# FPGA_Bank2-3.net
KiCad netlist of a schematic drawn in Altium Designer
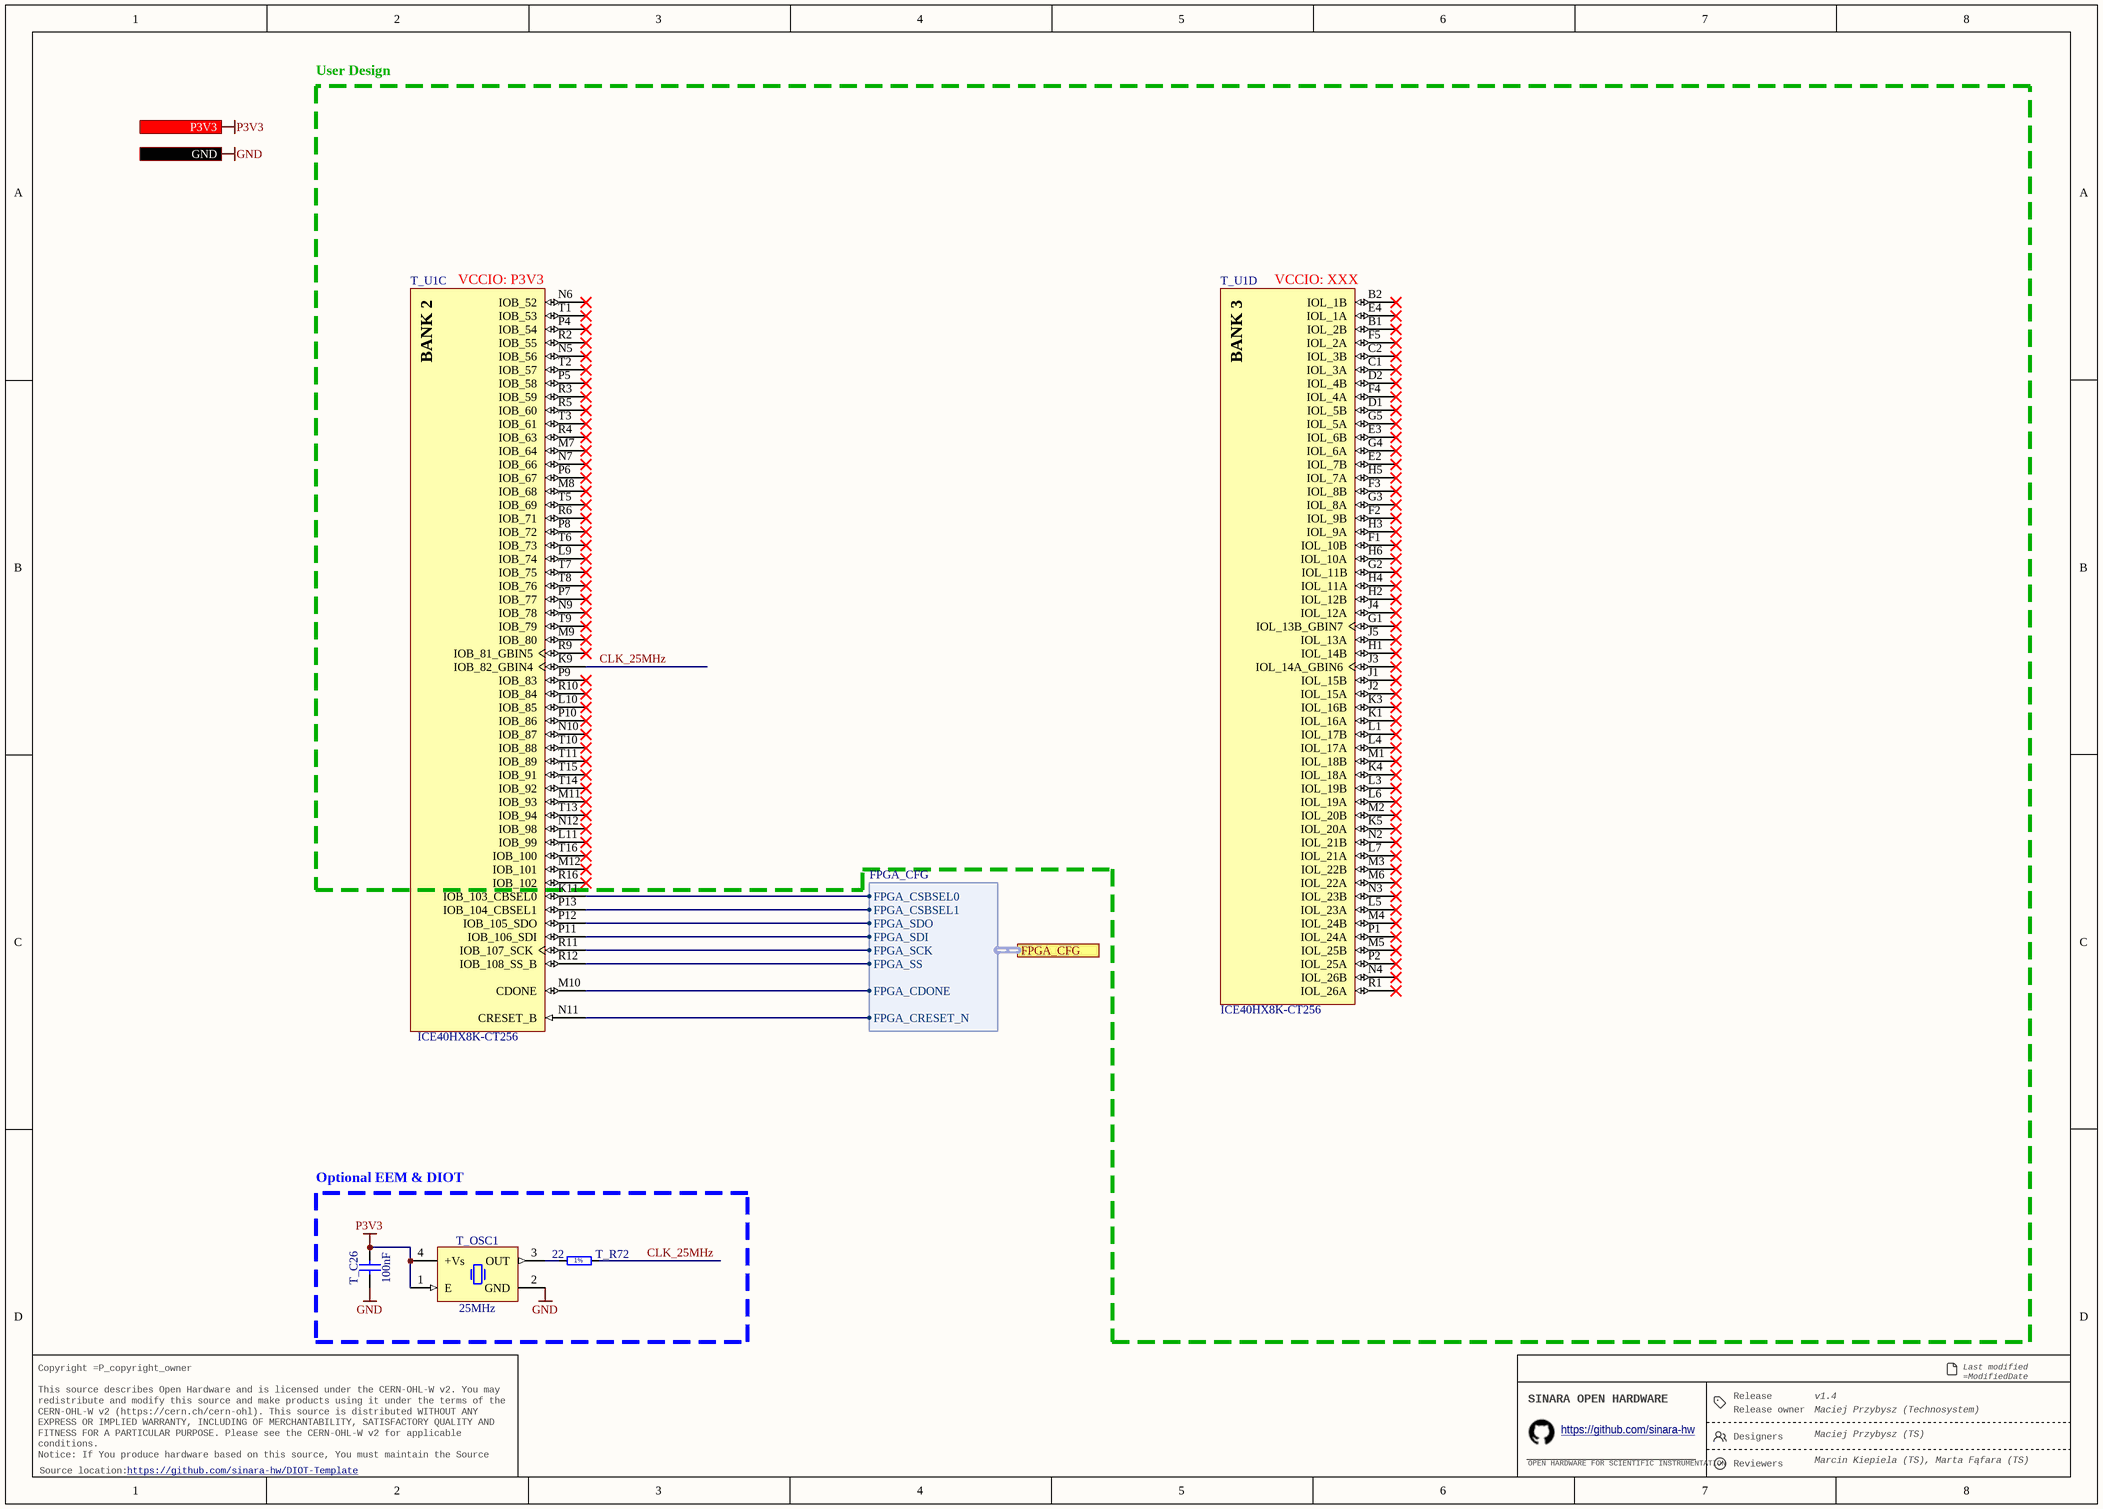
[diagram p0: FPGA_Bank2-3.SchDoc]

(export (version "E")
  (design (tool "Eeschema 10.0.6"))
  (components
    (comp (ref "T_C26")
      (value "100nF")
      (footprint "CAPC1005X55N")
      (description "Non-polarised capacitor")
      (fields
        (field (name "PART NUMBER") "CC0402_100NF_50V_10%_X7R")
        (field (name "VOLTAGE") "50V")
        (field (name "AUTHOR") "CERN DEM MR")
      )
      (libsource (lib "Capacitors") (part "Capacitor - non polarized"))
    )
    (comp (ref "T_OSC1")
      (value "25MHz")
      (footprint "OSC_IQD_CFPS-39")
      (description "Oscillator 4 pins 1=E 2=GND 3=OUT 4=+Vs")
      (fields
        (field (name "PART NUMBER") "OSC_25MHZ_IQD_LFSPXO025165")
        (field (name "MANUFACTURER") "IQD FREQUENCY PRODUCTS")
        (field (name "AUTHOR") "CERN DEM JLC")
      )
      (libsource (lib "ICs And Semiconductors") (part "Oscillator 1E 2GND 3OUT 4Vs"))
    )
    (comp (ref "T_R72")
      (value "22")
      (footprint "RESC1005X40N")
      (description "Resistor - 1%")
      (fields
        (field (name "PART NUMBER") "R0402_22R_1%_0.0625W_100PPM")
        (field (name "POWER") "0.0625W")
        (field (name "AUTHOR") "CERN DEM JLC")
      )
      (libsource (lib "Resistors") (part "Resistor - 1%"))
    )
    (comp (ref "T_U1")
      (value "ICE40HX8K-CT256")
      (footprint "LATC-caBGA-256")
      (fields (field (name "MANUFACTURER") "Lattice Semiconductor"))
      (libsource (lib "Altium Content Vault") (part "LATC-HX8K-caBGA-256"))
    )
  )
  (nets
    (net (code "2") (name "/CLK_25MHz") (class "Default")
      (node (ref "T_R72") (pin "2") (pinfunction "2_2") (pintype "passive"))
      (node (ref "T_U1") (pin "K9") (pinfunction "IOB_82_GBIN4_K9") (pintype "bidirectional"))
    )
    (net (code "3") (name "/FPGA_CDONE") (class "Default")
      (node (ref "T_U1") (pin "M10") (pinfunction "CDONE_M10") (pintype "bidirectional"))
    )
    (net (code "4") (name "/FPGA_CRESET_N") (class "Default")
      (node (ref "T_U1") (pin "N11") (pinfunction "CRESET_B_N11") (pintype "input"))
    )
    (net (code "5") (name "/FPGA_CSBSEL0") (class "Default")
      (node (ref "T_U1") (pin "K11") (pinfunction "IOB_103_CBSEL0_K11") (pintype "bidirectional"))
    )
    (net (code "6") (name "/FPGA_CSBSEL1") (class "Default")
      (node (ref "T_U1") (pin "P13") (pinfunction "IOB_104_CBSEL1_P13") (pintype "bidirectional"))
    )
    (net (code "7") (name "/FPGA_SCK") (class "Default")
      (node (ref "T_U1") (pin "R11") (pinfunction "IOB_107_SCK_R11") (pintype "bidirectional"))
    )
    (net (code "8") (name "/FPGA_SDI") (class "Default")
      (node (ref "T_U1") (pin "P11") (pinfunction "IOB_106_SDI_P11") (pintype "bidirectional"))
    )
    (net (code "9") (name "/FPGA_SDO") (class "Default")
      (node (ref "T_U1") (pin "P12") (pinfunction "IOB_105_SDO_P12") (pintype "bidirectional"))
    )
    (net (code "10") (name "/FPGA_SS") (class "Default")
      (node (ref "T_U1") (pin "R12") (pinfunction "IOB_108_SS_B_R12") (pintype "bidirectional"))
    )
    (net (code "12") (name "GND") (class "Default")
      (node (ref "T_C26") (pin "1") (pinfunction "1_1") (pintype "passive"))
      (node (ref "T_OSC1") (pin "2") (pinfunction "GND_2") (pintype "power_in"))
    )
    (net (code "13") (name "Net-(T_OSC1-OUT)") (class "Default")
      (node (ref "T_OSC1") (pin "3") (pinfunction "OUT_3") (pintype "output"))
      (node (ref "T_R72") (pin "1") (pinfunction "1_1") (pintype "passive"))
    )
    (net (code "14") (name "P3V3") (class "Default")
      (node (ref "T_C26") (pin "2") (pinfunction "2_2") (pintype "passive"))
      (node (ref "T_OSC1") (pin "1") (pinfunction "E_1") (pintype "input"))
      (node (ref "T_OSC1") (pin "4") (pinfunction "+Vs_4") (pintype "power_in"))
    )
    (net (code "15") (name "unconnected-(T_U1C-IOB_52-PadN6)") (class "Default")
      (node (ref "T_U1") (pin "N6") (pinfunction "IOB_52_N6") (pintype "bidirectional+no_connect"))
    )
    (net (code "16") (name "unconnected-(T_U1C-IOB_53-PadT1)") (class "Default")
      (node (ref "T_U1") (pin "T1") (pinfunction "IOB_53_T1") (pintype "bidirectional+no_connect"))
    )
    (net (code "17") (name "unconnected-(T_U1C-IOB_54-PadP4)") (class "Default")
      (node (ref "T_U1") (pin "P4") (pinfunction "IOB_54_P4") (pintype "bidirectional+no_connect"))
    )
    (net (code "18") (name "unconnected-(T_U1C-IOB_55-PadR2)") (class "Default")
      (node (ref "T_U1") (pin "R2") (pinfunction "IOB_55_R2") (pintype "bidirectional+no_connect"))
    )
    (net (code "19") (name "unconnected-(T_U1C-IOB_56-PadN5)") (class "Default")
      (node (ref "T_U1") (pin "N5") (pinfunction "IOB_56_N5") (pintype "bidirectional+no_connect"))
    )
    (net (code "20") (name "unconnected-(T_U1C-IOB_57-PadT2)") (class "Default")
      (node (ref "T_U1") (pin "T2") (pinfunction "IOB_57_T2") (pintype "bidirectional+no_connect"))
    )
    (net (code "21") (name "unconnected-(T_U1C-IOB_58-PadP5)") (class "Default")
      (node (ref "T_U1") (pin "P5") (pinfunction "IOB_58_P5") (pintype "bidirectional+no_connect"))
    )
    (net (code "22") (name "unconnected-(T_U1C-IOB_59-PadR3)") (class "Default")
      (node (ref "T_U1") (pin "R3") (pinfunction "IOB_59_R3") (pintype "bidirectional+no_connect"))
    )
    (net (code "23") (name "unconnected-(T_U1C-IOB_60-PadR5)") (class "Default")
      (node (ref "T_U1") (pin "R5") (pinfunction "IOB_60_R5") (pintype "bidirectional+no_connect"))
    )
    (net (code "24") (name "unconnected-(T_U1C-IOB_61-PadT3)") (class "Default")
      (node (ref "T_U1") (pin "T3") (pinfunction "IOB_61_T3") (pintype "bidirectional+no_connect"))
    )
    (net (code "25") (name "unconnected-(T_U1C-IOB_63-PadR4)") (class "Default")
      (node (ref "T_U1") (pin "R4") (pinfunction "IOB_63_R4") (pintype "bidirectional+no_connect"))
    )
    (net (code "26") (name "unconnected-(T_U1C-IOB_64-PadM7)") (class "Default")
      (node (ref "T_U1") (pin "M7") (pinfunction "IOB_64_M7") (pintype "bidirectional+no_connect"))
    )
    (net (code "27") (name "unconnected-(T_U1C-IOB_66-PadN7)") (class "Default")
      (node (ref "T_U1") (pin "N7") (pinfunction "IOB_66_N7") (pintype "bidirectional+no_connect"))
    )
    (net (code "28") (name "unconnected-(T_U1C-IOB_67-PadP6)") (class "Default")
      (node (ref "T_U1") (pin "P6") (pinfunction "IOB_67_P6") (pintype "bidirectional+no_connect"))
    )
    (net (code "29") (name "unconnected-(T_U1C-IOB_68-PadM8)") (class "Default")
      (node (ref "T_U1") (pin "M8") (pinfunction "IOB_68_M8") (pintype "bidirectional+no_connect"))
    )
    (net (code "30") (name "unconnected-(T_U1C-IOB_69-PadT5)") (class "Default")
      (node (ref "T_U1") (pin "T5") (pinfunction "IOB_69_T5") (pintype "bidirectional+no_connect"))
    )
    (net (code "31") (name "unconnected-(T_U1C-IOB_71-PadR6)") (class "Default")
      (node (ref "T_U1") (pin "R6") (pinfunction "IOB_71_R6") (pintype "bidirectional+no_connect"))
    )
    (net (code "32") (name "unconnected-(T_U1C-IOB_72-PadP8)") (class "Default")
      (node (ref "T_U1") (pin "P8") (pinfunction "IOB_72_P8") (pintype "bidirectional+no_connect"))
    )
    (net (code "33") (name "unconnected-(T_U1C-IOB_73-PadT6)") (class "Default")
      (node (ref "T_U1") (pin "T6") (pinfunction "IOB_73_T6") (pintype "bidirectional+no_connect"))
    )
    (net (code "34") (name "unconnected-(T_U1C-IOB_74-PadL9)") (class "Default")
      (node (ref "T_U1") (pin "L9") (pinfunction "IOB_74_L9") (pintype "bidirectional+no_connect"))
    )
    (net (code "35") (name "unconnected-(T_U1C-IOB_75-PadT7)") (class "Default")
      (node (ref "T_U1") (pin "T7") (pinfunction "IOB_75_T7") (pintype "bidirectional+no_connect"))
    )
    (net (code "36") (name "unconnected-(T_U1C-IOB_76-PadT8)") (class "Default")
      (node (ref "T_U1") (pin "T8") (pinfunction "IOB_76_T8") (pintype "bidirectional+no_connect"))
    )
    (net (code "37") (name "unconnected-(T_U1C-IOB_77-PadP7)") (class "Default")
      (node (ref "T_U1") (pin "P7") (pinfunction "IOB_77_P7") (pintype "bidirectional+no_connect"))
    )
    (net (code "38") (name "unconnected-(T_U1C-IOB_78-PadN9)") (class "Default")
      (node (ref "T_U1") (pin "N9") (pinfunction "IOB_78_N9") (pintype "bidirectional+no_connect"))
    )
    (net (code "39") (name "unconnected-(T_U1C-IOB_79-PadT9)") (class "Default")
      (node (ref "T_U1") (pin "T9") (pinfunction "IOB_79_T9") (pintype "bidirectional+no_connect"))
    )
    (net (code "40") (name "unconnected-(T_U1C-IOB_80-PadM9)") (class "Default")
      (node (ref "T_U1") (pin "M9") (pinfunction "IOB_80_M9") (pintype "bidirectional+no_connect"))
    )
    (net (code "41") (name "unconnected-(T_U1C-IOB_81_GBIN5-PadR9)") (class "Default")
      (node (ref "T_U1") (pin "R9") (pinfunction "IOB_81_GBIN5_R9") (pintype "bidirectional+no_connect"))
    )
    (net (code "42") (name "unconnected-(T_U1C-IOB_83-PadP9)") (class "Default")
      (node (ref "T_U1") (pin "P9") (pinfunction "IOB_83_P9") (pintype "bidirectional+no_connect"))
    )
    (net (code "43") (name "unconnected-(T_U1C-IOB_84-PadR10)") (class "Default")
      (node (ref "T_U1") (pin "R10") (pinfunction "IOB_84_R10") (pintype "bidirectional+no_connect"))
    )
    (net (code "44") (name "unconnected-(T_U1C-IOB_85-PadL10)") (class "Default")
      (node (ref "T_U1") (pin "L10") (pinfunction "IOB_85_L10") (pintype "bidirectional+no_connect"))
    )
    (net (code "45") (name "unconnected-(T_U1C-IOB_86-PadP10)") (class "Default")
      (node (ref "T_U1") (pin "P10") (pinfunction "IOB_86_P10") (pintype "bidirectional+no_connect"))
    )
    (net (code "46") (name "unconnected-(T_U1C-IOB_87-PadN10)") (class "Default")
      (node (ref "T_U1") (pin "N10") (pinfunction "IOB_87_N10") (pintype "bidirectional+no_connect"))
    )
    (net (code "47") (name "unconnected-(T_U1C-IOB_88-PadT10)") (class "Default")
      (node (ref "T_U1") (pin "T10") (pinfunction "IOB_88_T10") (pintype "bidirectional+no_connect"))
    )
    (net (code "48") (name "unconnected-(T_U1C-IOB_89-PadT11)") (class "Default")
      (node (ref "T_U1") (pin "T11") (pinfunction "IOB_89_T11") (pintype "bidirectional+no_connect"))
    )
    (net (code "49") (name "unconnected-(T_U1C-IOB_91-PadT15)") (class "Default")
      (node (ref "T_U1") (pin "T15") (pinfunction "IOB_91_T15") (pintype "bidirectional+no_connect"))
    )
    (net (code "50") (name "unconnected-(T_U1C-IOB_92-PadT14)") (class "Default")
      (node (ref "T_U1") (pin "T14") (pinfunction "IOB_92_T14") (pintype "bidirectional+no_connect"))
    )
    (net (code "51") (name "unconnected-(T_U1C-IOB_93-PadM11)") (class "Default")
      (node (ref "T_U1") (pin "M11") (pinfunction "IOB_93_M11") (pintype "bidirectional+no_connect"))
    )
    (net (code "52") (name "unconnected-(T_U1C-IOB_94-PadT13)") (class "Default")
      (node (ref "T_U1") (pin "T13") (pinfunction "IOB_94_T13") (pintype "bidirectional+no_connect"))
    )
    (net (code "53") (name "unconnected-(T_U1C-IOB_98-PadN12)") (class "Default")
      (node (ref "T_U1") (pin "N12") (pinfunction "IOB_98_N12") (pintype "bidirectional+no_connect"))
    )
    (net (code "54") (name "unconnected-(T_U1C-IOB_99-PadL11)") (class "Default")
      (node (ref "T_U1") (pin "L11") (pinfunction "IOB_99_L11") (pintype "bidirectional+no_connect"))
    )
    (net (code "55") (name "unconnected-(T_U1C-IOB_100-PadT16)") (class "Default")
      (node (ref "T_U1") (pin "T16") (pinfunction "IOB_100_T16") (pintype "bidirectional+no_connect"))
    )
    (net (code "56") (name "unconnected-(T_U1C-IOB_101-PadM12)") (class "Default")
      (node (ref "T_U1") (pin "M12") (pinfunction "IOB_101_M12") (pintype "bidirectional+no_connect"))
    )
    (net (code "57") (name "unconnected-(T_U1C-IOB_102-PadR16)") (class "Default")
      (node (ref "T_U1") (pin "R16") (pinfunction "IOB_102_R16") (pintype "bidirectional+no_connect"))
    )
    (net (code "58") (name "unconnected-(T_U1D-IOL_1A-PadE4)") (class "Default")
      (node (ref "T_U1") (pin "E4") (pinfunction "IOL_1A_E4") (pintype "bidirectional+no_connect"))
    )
    (net (code "59") (name "unconnected-(T_U1D-IOL_1B-PadB2)") (class "Default")
      (node (ref "T_U1") (pin "B2") (pinfunction "IOL_1B_B2") (pintype "bidirectional+no_connect"))
    )
    (net (code "60") (name "unconnected-(T_U1D-IOL_2A-PadF5)") (class "Default")
      (node (ref "T_U1") (pin "F5") (pinfunction "IOL_2A_F5") (pintype "bidirectional+no_connect"))
    )
    (net (code "61") (name "unconnected-(T_U1D-IOL_2B-PadB1)") (class "Default")
      (node (ref "T_U1") (pin "B1") (pinfunction "IOL_2B_B1") (pintype "bidirectional+no_connect"))
    )
    (net (code "62") (name "unconnected-(T_U1D-IOL_3A-PadC1)") (class "Default")
      (node (ref "T_U1") (pin "C1") (pinfunction "IOL_3A_C1") (pintype "bidirectional+no_connect"))
    )
    (net (code "63") (name "unconnected-(T_U1D-IOL_3B-PadC2)") (class "Default")
      (node (ref "T_U1") (pin "C2") (pinfunction "IOL_3B_C2") (pintype "bidirectional+no_connect"))
    )
    (net (code "64") (name "unconnected-(T_U1D-IOL_4A-PadF4)") (class "Default")
      (node (ref "T_U1") (pin "F4") (pinfunction "IOL_4A_F4") (pintype "bidirectional+no_connect"))
    )
    (net (code "65") (name "unconnected-(T_U1D-IOL_4B-PadD2)") (class "Default")
      (node (ref "T_U1") (pin "D2") (pinfunction "IOL_4B_D2") (pintype "bidirectional+no_connect"))
    )
    (net (code "66") (name "unconnected-(T_U1D-IOL_5A-PadG5)") (class "Default")
      (node (ref "T_U1") (pin "G5") (pinfunction "IOL_5A_G5") (pintype "bidirectional+no_connect"))
    )
    (net (code "67") (name "unconnected-(T_U1D-IOL_5B-PadD1)") (class "Default")
      (node (ref "T_U1") (pin "D1") (pinfunction "IOL_5B_D1") (pintype "bidirectional+no_connect"))
    )
    (net (code "68") (name "unconnected-(T_U1D-IOL_6A-PadG4)") (class "Default")
      (node (ref "T_U1") (pin "G4") (pinfunction "IOL_6A_G4") (pintype "bidirectional+no_connect"))
    )
    (net (code "69") (name "unconnected-(T_U1D-IOL_6B-PadE3)") (class "Default")
      (node (ref "T_U1") (pin "E3") (pinfunction "IOL_6B_E3") (pintype "bidirectional+no_connect"))
    )
    (net (code "70") (name "unconnected-(T_U1D-IOL_7A-PadH5)") (class "Default")
      (node (ref "T_U1") (pin "H5") (pinfunction "IOL_7A_H5") (pintype "bidirectional+no_connect"))
    )
    (net (code "71") (name "unconnected-(T_U1D-IOL_7B-PadE2)") (class "Default")
      (node (ref "T_U1") (pin "E2") (pinfunction "IOL_7B_E2") (pintype "bidirectional+no_connect"))
    )
    (net (code "72") (name "unconnected-(T_U1D-IOL_8A-PadG3)") (class "Default")
      (node (ref "T_U1") (pin "G3") (pinfunction "IOL_8A_G3") (pintype "bidirectional+no_connect"))
    )
    (net (code "73") (name "unconnected-(T_U1D-IOL_8B-PadF3)") (class "Default")
      (node (ref "T_U1") (pin "F3") (pinfunction "IOL_8B_F3") (pintype "bidirectional+no_connect"))
    )
    (net (code "74") (name "unconnected-(T_U1D-IOL_9A-PadH3)") (class "Default")
      (node (ref "T_U1") (pin "H3") (pinfunction "IOL_9A_H3") (pintype "bidirectional+no_connect"))
    )
    (net (code "75") (name "unconnected-(T_U1D-IOL_9B-PadF2)") (class "Default")
      (node (ref "T_U1") (pin "F2") (pinfunction "IOL_9B_F2") (pintype "bidirectional+no_connect"))
    )
    (net (code "76") (name "unconnected-(T_U1D-IOL_10A-PadH6)") (class "Default")
      (node (ref "T_U1") (pin "H6") (pinfunction "IOL_10A_H6") (pintype "bidirectional+no_connect"))
    )
    (net (code "77") (name "unconnected-(T_U1D-IOL_10B-PadF1)") (class "Default")
      (node (ref "T_U1") (pin "F1") (pinfunction "IOL_10B_F1") (pintype "bidirectional+no_connect"))
    )
    (net (code "78") (name "unconnected-(T_U1D-IOL_11A-PadH4)") (class "Default")
      (node (ref "T_U1") (pin "H4") (pinfunction "IOL_11A_H4") (pintype "bidirectional+no_connect"))
    )
    (net (code "79") (name "unconnected-(T_U1D-IOL_11B-PadG2)") (class "Default")
      (node (ref "T_U1") (pin "G2") (pinfunction "IOL_11B_G2") (pintype "bidirectional+no_connect"))
    )
    (net (code "80") (name "unconnected-(T_U1D-IOL_12A-PadJ4)") (class "Default")
      (node (ref "T_U1") (pin "J4") (pinfunction "IOL_12A_J4") (pintype "bidirectional+no_connect"))
    )
    (net (code "81") (name "unconnected-(T_U1D-IOL_12B-PadH2)") (class "Default")
      (node (ref "T_U1") (pin "H2") (pinfunction "IOL_12B_H2") (pintype "bidirectional+no_connect"))
    )
    (net (code "82") (name "unconnected-(T_U1D-IOL_13A-PadJ5)") (class "Default")
      (node (ref "T_U1") (pin "J5") (pinfunction "IOL_13A_J5") (pintype "bidirectional+no_connect"))
    )
    (net (code "83") (name "unconnected-(T_U1D-IOL_13B_GBIN7-PadG1)") (class "Default")
      (node (ref "T_U1") (pin "G1") (pinfunction "IOL_13B_GBIN7_G1") (pintype "bidirectional+no_connect"))
    )
    (net (code "84") (name "unconnected-(T_U1D-IOL_14A_GBIN6-PadJ3)") (class "Default")
      (node (ref "T_U1") (pin "J3") (pinfunction "IOL_14A_GBIN6_J3") (pintype "bidirectional+no_connect"))
    )
    (net (code "85") (name "unconnected-(T_U1D-IOL_14B-PadH1)") (class "Default")
      (node (ref "T_U1") (pin "H1") (pinfunction "IOL_14B_H1") (pintype "bidirectional+no_connect"))
    )
    (net (code "86") (name "unconnected-(T_U1D-IOL_15A-PadJ2)") (class "Default")
      (node (ref "T_U1") (pin "J2") (pinfunction "IOL_15A_J2") (pintype "bidirectional+no_connect"))
    )
    (net (code "87") (name "unconnected-(T_U1D-IOL_15B-PadJ1)") (class "Default")
      (node (ref "T_U1") (pin "J1") (pinfunction "IOL_15B_J1") (pintype "bidirectional+no_connect"))
    )
    (net (code "88") (name "unconnected-(T_U1D-IOL_16A-PadK1)") (class "Default")
      (node (ref "T_U1") (pin "K1") (pinfunction "IOL_16A_K1") (pintype "bidirectional+no_connect"))
    )
    (net (code "89") (name "unconnected-(T_U1D-IOL_16B-PadK3)") (class "Default")
      (node (ref "T_U1") (pin "K3") (pinfunction "IOL_16B_K3") (pintype "bidirectional+no_connect"))
    )
    (net (code "90") (name "unconnected-(T_U1D-IOL_17A-PadL4)") (class "Default")
      (node (ref "T_U1") (pin "L4") (pinfunction "IOL_17A_L4") (pintype "bidirectional+no_connect"))
    )
    (net (code "91") (name "unconnected-(T_U1D-IOL_17B-PadL1)") (class "Default")
      (node (ref "T_U1") (pin "L1") (pinfunction "IOL_17B_L1") (pintype "bidirectional+no_connect"))
    )
    (net (code "92") (name "unconnected-(T_U1D-IOL_18A-PadK4)") (class "Default")
      (node (ref "T_U1") (pin "K4") (pinfunction "IOL_18A_K4") (pintype "bidirectional+no_connect"))
    )
    (net (code "93") (name "unconnected-(T_U1D-IOL_18B-PadM1)") (class "Default")
      (node (ref "T_U1") (pin "M1") (pinfunction "IOL_18B_M1") (pintype "bidirectional+no_connect"))
    )
    (net (code "94") (name "unconnected-(T_U1D-IOL_19A-PadL6)") (class "Default")
      (node (ref "T_U1") (pin "L6") (pinfunction "IOL_19A_L6") (pintype "bidirectional+no_connect"))
    )
    (net (code "95") (name "unconnected-(T_U1D-IOL_19B-PadL3)") (class "Default")
      (node (ref "T_U1") (pin "L3") (pinfunction "IOL_19B_L3") (pintype "bidirectional+no_connect"))
    )
    (net (code "96") (name "unconnected-(T_U1D-IOL_20A-PadK5)") (class "Default")
      (node (ref "T_U1") (pin "K5") (pinfunction "IOL_20A_K5") (pintype "bidirectional+no_connect"))
    )
    (net (code "97") (name "unconnected-(T_U1D-IOL_20B-PadM2)") (class "Default")
      (node (ref "T_U1") (pin "M2") (pinfunction "IOL_20B_M2") (pintype "bidirectional+no_connect"))
    )
    (net (code "98") (name "unconnected-(T_U1D-IOL_21A-PadL7)") (class "Default")
      (node (ref "T_U1") (pin "L7") (pinfunction "IOL_21A_L7") (pintype "bidirectional+no_connect"))
    )
    (net (code "99") (name "unconnected-(T_U1D-IOL_21B-PadN2)") (class "Default")
      (node (ref "T_U1") (pin "N2") (pinfunction "IOL_21B_N2") (pintype "bidirectional+no_connect"))
    )
    (net (code "100") (name "unconnected-(T_U1D-IOL_22A-PadM6)") (class "Default")
      (node (ref "T_U1") (pin "M6") (pinfunction "IOL_22A_M6") (pintype "bidirectional+no_connect"))
    )
    (net (code "101") (name "unconnected-(T_U1D-IOL_22B-PadM3)") (class "Default")
      (node (ref "T_U1") (pin "M3") (pinfunction "IOL_22B_M3") (pintype "bidirectional+no_connect"))
    )
    (net (code "102") (name "unconnected-(T_U1D-IOL_23A-PadL5)") (class "Default")
      (node (ref "T_U1") (pin "L5") (pinfunction "IOL_23A_L5") (pintype "bidirectional+no_connect"))
    )
    (net (code "103") (name "unconnected-(T_U1D-IOL_23B-PadN3)") (class "Default")
      (node (ref "T_U1") (pin "N3") (pinfunction "IOL_23B_N3") (pintype "bidirectional+no_connect"))
    )
    (net (code "104") (name "unconnected-(T_U1D-IOL_24A-PadP1)") (class "Default")
      (node (ref "T_U1") (pin "P1") (pinfunction "IOL_24A_P1") (pintype "bidirectional+no_connect"))
    )
    (net (code "105") (name "unconnected-(T_U1D-IOL_24B-PadM4)") (class "Default")
      (node (ref "T_U1") (pin "M4") (pinfunction "IOL_24B_M4") (pintype "bidirectional+no_connect"))
    )
    (net (code "106") (name "unconnected-(T_U1D-IOL_25A-PadP2)") (class "Default")
      (node (ref "T_U1") (pin "P2") (pinfunction "IOL_25A_P2") (pintype "bidirectional+no_connect"))
    )
    (net (code "107") (name "unconnected-(T_U1D-IOL_25B-PadM5)") (class "Default")
      (node (ref "T_U1") (pin "M5") (pinfunction "IOL_25B_M5") (pintype "bidirectional+no_connect"))
    )
    (net (code "108") (name "unconnected-(T_U1D-IOL_26A-PadR1)") (class "Default")
      (node (ref "T_U1") (pin "R1") (pinfunction "IOL_26A_R1") (pintype "bidirectional+no_connect"))
    )
    (net (code "109") (name "unconnected-(T_U1D-IOL_26B-PadN4)") (class "Default")
      (node (ref "T_U1") (pin "N4") (pinfunction "IOL_26B_N4") (pintype "bidirectional+no_connect"))
    )
  )
)
